# Connector_Card.net
KiCad netlist of a schematic drawn in Altium Designer
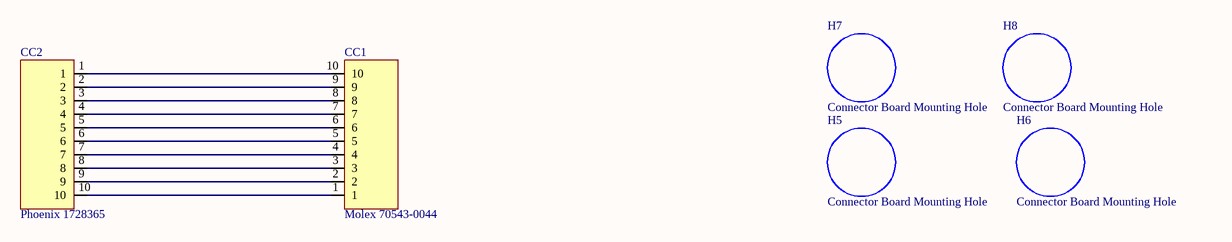
[diagram p0: Connector_Card.SchDoc]

(export (version "E")
  (design (tool "Eeschema 10.0.6"))
  (components
    (comp (ref "CC1")
      (value "Molex 70543-0044")
      (footprint "10 Pin Molex Vertical")
      (description "Molex SL Vertical 1 x 10 header")
      (fields (field (name "MFR") "Molex"))
      (libsource (lib "Custom Components") (part "Molex 70543-0044"))
    )
    (comp (ref "CC2")
      (value "Phoenix 1728365")
      (footprint "Phoenix 1728365")
      (description "Phoenix PCB Connector, 1 x 10 pins")
      (fields (field (name "MFR") "Phoenix"))
      (libsource (lib "Custom Components") (part "Phoenix 1728365"))
    )
    (comp (ref "H5")
      (value "Connector Board Mounting Hole")
      (footprint "Mount Hole Connector Board")
      (libsource (lib "Custom Components") (part "Connector Board Mounting Hole"))
    )
    (comp (ref "H6")
      (value "Connector Board Mounting Hole")
      (footprint "Mount Hole Connector Board")
      (libsource (lib "Custom Components") (part "Connector Board Mounting Hole"))
    )
    (comp (ref "H7")
      (value "Connector Board Mounting Hole")
      (footprint "Mount Hole Connector Board")
      (libsource (lib "Custom Components") (part "Connector Board Mounting Hole"))
    )
    (comp (ref "H8")
      (value "Connector Board Mounting Hole")
      (footprint "Mount Hole Connector Board")
      (libsource (lib "Custom Components") (part "Connector Board Mounting Hole"))
    )
  )
  (nets
    (net (code "1") (name "Net-(CC1-Pad1)") (class "Default")
      (node (ref "CC1") (pin "1") (pinfunction "1_1") (pintype "passive"))
      (node (ref "CC2") (pin "10") (pinfunction "10_10") (pintype "passive"))
    )
    (net (code "2") (name "Net-(CC1-Pad2)") (class "Default")
      (node (ref "CC1") (pin "2") (pinfunction "2_2") (pintype "passive"))
      (node (ref "CC2") (pin "9") (pinfunction "9_9") (pintype "passive"))
    )
    (net (code "3") (name "Net-(CC1-Pad3)") (class "Default")
      (node (ref "CC1") (pin "3") (pinfunction "3_3") (pintype "passive"))
      (node (ref "CC2") (pin "8") (pinfunction "8_8") (pintype "passive"))
    )
    (net (code "4") (name "Net-(CC1-Pad4)") (class "Default")
      (node (ref "CC1") (pin "4") (pinfunction "4_4") (pintype "passive"))
      (node (ref "CC2") (pin "7") (pinfunction "7_7") (pintype "passive"))
    )
    (net (code "5") (name "Net-(CC1-Pad5)") (class "Default")
      (node (ref "CC1") (pin "5") (pinfunction "5_5") (pintype "passive"))
      (node (ref "CC2") (pin "6") (pinfunction "6_6") (pintype "passive"))
    )
    (net (code "6") (name "Net-(CC1-Pad6)") (class "Default")
      (node (ref "CC1") (pin "6") (pinfunction "6_6") (pintype "passive"))
      (node (ref "CC2") (pin "5") (pinfunction "5_5") (pintype "passive"))
    )
    (net (code "7") (name "Net-(CC1-Pad7)") (class "Default")
      (node (ref "CC1") (pin "7") (pinfunction "7_7") (pintype "passive"))
      (node (ref "CC2") (pin "4") (pinfunction "4_4") (pintype "passive"))
    )
    (net (code "8") (name "Net-(CC1-Pad8)") (class "Default")
      (node (ref "CC1") (pin "8") (pinfunction "8_8") (pintype "passive"))
      (node (ref "CC2") (pin "3") (pinfunction "3_3") (pintype "passive"))
    )
    (net (code "9") (name "Net-(CC1-Pad9)") (class "Default")
      (node (ref "CC1") (pin "9") (pinfunction "9_9") (pintype "passive"))
      (node (ref "CC2") (pin "2") (pinfunction "2_2") (pintype "passive"))
    )
    (net (code "10") (name "Net-(CC1-Pad10)") (class "Default")
      (node (ref "CC1") (pin "10") (pinfunction "10_10") (pintype "passive"))
      (node (ref "CC2") (pin "1") (pinfunction "1_1") (pintype "passive"))
    )
  )
)
